# short_circuit_protection.net
KiCad netlist of a schematic drawn in Altium Designer
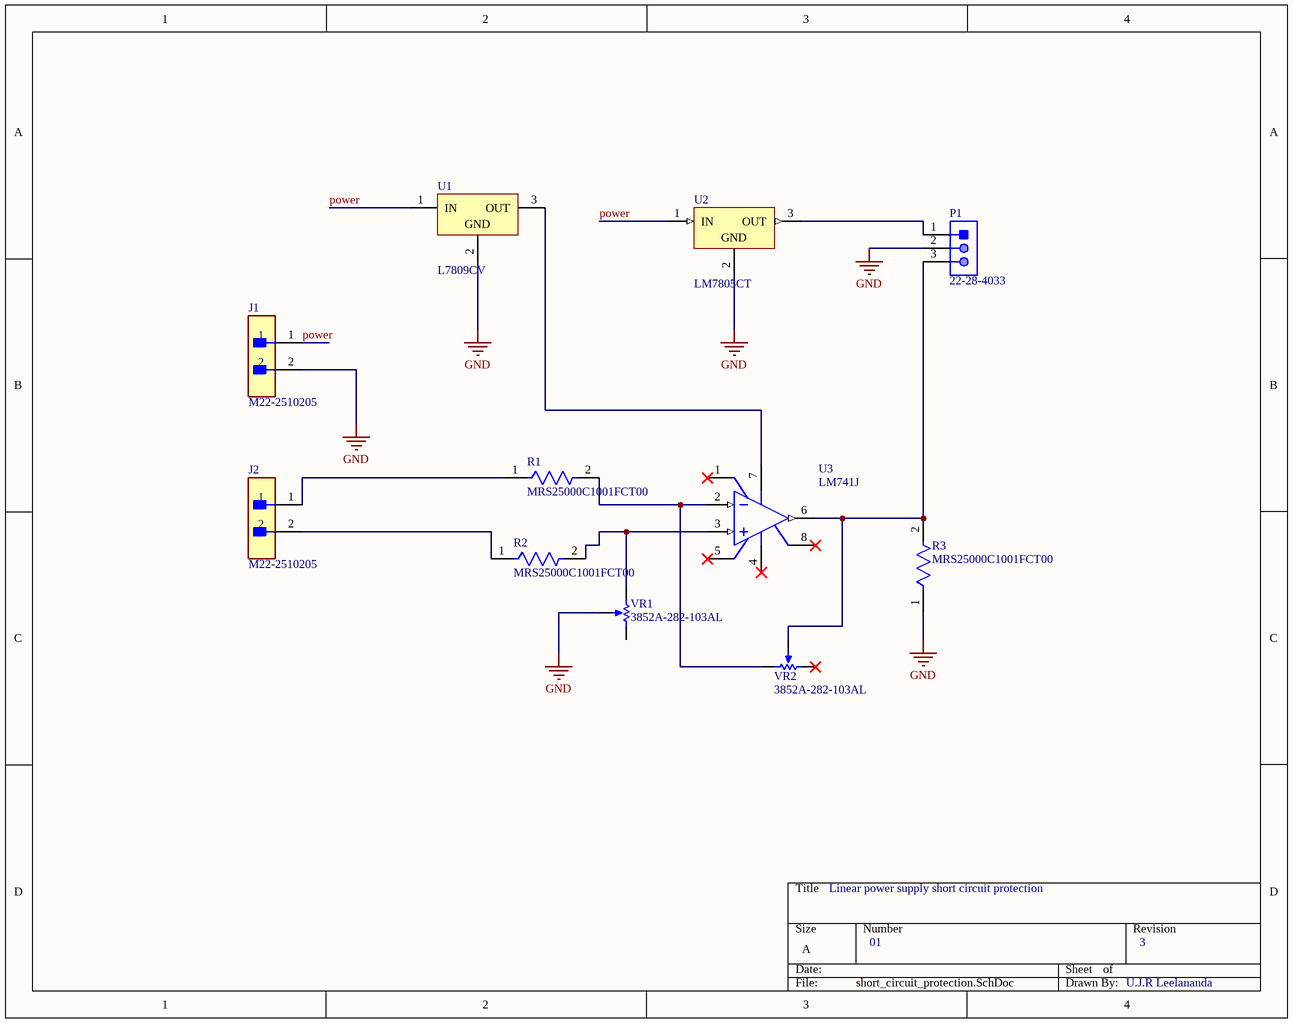
[diagram p0: short_circuit_protection.SchDoc]

(export (version "E")
  (design (tool "Eeschema 10.0.6"))
  (components
    (comp (ref "J1")
      (value "M22-2510205")
      (footprint "FP-M22-2510205-MFG")
      (description "CONN HEADER VERT 2POS 2MM")
      (fields
        (field (name "MANUFACTURER") "Harwin")
        (field (name "OCTOPART") "https://octopart.com/m22-2510205-harwin-2538221")
      )
      (libsource (lib "Altium Content Vault") (part "3bc925449376181038e59eaffc5286c"))
    )
    (comp (ref "J2")
      (value "M22-2510205")
      (footprint "FP-M22-2510205-MFG")
      (description "CONN HEADER VERT 2POS 2MM")
      (fields
        (field (name "MANUFACTURER") "Harwin")
        (field (name "OCTOPART") "https://octopart.com/m22-2510205-harwin-2538221")
      )
      (libsource (lib "Altium Content Vault") (part "3bc925449376181038e59eaffc5286c"))
    )
    (comp (ref "P1")
      (value "22-28-4033")
      (footprint "MOLX-22-28-4033_V")
      (description "Male Header, Pitch 2.54 mm, 1 x 3 Position, Height 8.38 mm, Tail Length 3.18 mm, RoHS, Bulk")
      (fields (field (name "MANUFACTURER") "Molex"))
      (libsource (lib "Altium Content Vault") (part "CN-1P-M-R3"))
    )
    (comp (ref "R1")
      (value "MRS25000C1001FCT00")
      (footprint "FP-MRS25-MFG")
      (description "RES 1K OHM 0.6W 1% AXIAL")
      (fields (field (name "TOLERANCE") "1%"))
      (libsource (lib "Altium Content Vault") (part "1029c3af85768c4190bb7ad29bc67b5"))
    )
    (comp (ref "R2")
      (value "MRS25000C1001FCT00")
      (footprint "FP-MRS25-MFG")
      (description "RES 1K OHM 0.6W 1% AXIAL")
      (fields (field (name "TOLERANCE") "1%"))
      (libsource (lib "Altium Content Vault") (part "1029c3af85768c4190bb7ad29bc67b5"))
    )
    (comp (ref "R3")
      (value "MRS25000C1001FCT00")
      (footprint "FP-MRS25-MFG")
      (description "RES 1K OHM 0.6W 1% AXIAL")
      (fields (field (name "TOLERANCE") "1%"))
      (libsource (lib "Altium Content Vault") (part "1029c3af85768c4190bb7ad29bc67b5"))
    )
    (comp (ref "U1")
      (value "L7809CV")
      (footprint "TO220")
      (description "Positive Voltage Regulator, 9V, 3-Pin TO-220")
      (libsource (lib "Altium Content Vault") (part "PM-REG-L4940-SIL3"))
    )
    (comp (ref "U2")
      (value "LM7805CT")
      (footprint "FAIR-TO-220-3")
      (description "Positive Voltage Regulator, 5 V, 1 A, -40 to 125 degC, 3-Pin TO-220, RoHS, Tube")
      (fields (field (name "MANUFACTURER") "FairchildSemiconductor"))
      (libsource (lib "Altium Content Vault") (part "FAIR-LM7805CT-TO220-3"))
    )
    (comp (ref "U3")
      (value "LM741J")
      (footprint "NAB0008A")
      (description "Operational Amplifier, 8-pin CerDIP")
      (fields (field (name "MANUFACTURER") "Texas Instruments"))
      (libsource (lib "Altium Content Vault") (part "AMP-OPA-LM741-8"))
    )
    (comp (ref "VR1")
      (value "3852A-282-103AL")
      (footprint "BOUR-3852A-282-103AL-3_V")
      (description "Diameter Panel Control, 10 KOhm, +/- 10%, 2 W, -1 to 125 degC, 3-Pin THD, RoHS, Bulk")
      (fields (field (name "TOLERANCE") "±10%") (field (name "MANUFACTURER") "Bourns"))
      (libsource (lib "Altium Content Vault") (part "RES-POT-3"))
    )
    (comp (ref "VR2")
      (value "3852A-282-103AL")
      (footprint "BOUR-3852A-282-103AL-3_V")
      (description "Diameter Panel Control, 10 KOhm, +/- 10%, 2 W, -1 to 125 degC, 3-Pin THD, RoHS, Bulk")
      (fields (field (name "TOLERANCE") "±10%") (field (name "MANUFACTURER") "Bourns"))
      (libsource (lib "Altium Content Vault") (part "RES-POT-3"))
    )
  )
  (nets
    (net (code "1") (name "/power") (class "Default")
      (node (ref "J1") (pin "1") (pinfunction "1_1") (pintype "passive"))
      (node (ref "U1") (pin "1") (pinfunction "IN_1") (pintype "power_in"))
      (node (ref "U2") (pin "1") (pinfunction "IN_1") (pintype "input"))
    )
    (net (code "2") (name "GND") (class "Default")
      (node (ref "J1") (pin "2") (pinfunction "2_2") (pintype "passive"))
      (node (ref "P1") (pin "2") (pinfunction "2_2") (pintype "passive"))
      (node (ref "R3") (pin "1") (pinfunction "1_1") (pintype "passive"))
      (node (ref "U1") (pin "2") (pinfunction "GND_2") (pintype "power_in"))
      (node (ref "U2") (pin "2") (pinfunction "GND_2") (pintype "power_in"))
      (node (ref "VR1") (pin "2") (pinfunction "S_2") (pintype "passive"))
    )
    (net (code "3") (name "Net-(J2-Pad1)") (class "Default")
      (node (ref "J2") (pin "1") (pinfunction "1_1") (pintype "passive"))
      (node (ref "R1") (pin "1") (pinfunction "1_1") (pintype "passive"))
    )
    (net (code "4") (name "Net-(J2-Pad2)") (class "Default")
      (node (ref "J2") (pin "2") (pinfunction "2_2") (pintype "passive"))
      (node (ref "R2") (pin "1") (pinfunction "1_1") (pintype "passive"))
    )
    (net (code "5") (name "Net-(U1-OUT)") (class "Default")
      (node (ref "U1") (pin "3") (pinfunction "OUT_3") (pintype "power_in"))
      (node (ref "U3") (pin "7") (pinfunction "V+_7") (pintype "power_in"))
    )
    (net (code "6") (name "Net-(U2-OUT)") (class "Default")
      (node (ref "P1") (pin "1") (pinfunction "1_1") (pintype "passive"))
      (node (ref "U2") (pin "3") (pinfunction "OUT_3") (pintype "output"))
    )
    (net (code "7") (name "Net-(U3-IN+)") (class "Default")
      (node (ref "R2") (pin "2") (pinfunction "2_2") (pintype "passive"))
      (node (ref "U3") (pin "3") (pinfunction "IN+_3") (pintype "input"))
      (node (ref "VR1") (pin "1") (pinfunction "CCW_1") (pintype "passive"))
    )
    (net (code "8") (name "Net-(U3-IN-)") (class "Default")
      (node (ref "R1") (pin "2") (pinfunction "2_2") (pintype "passive"))
      (node (ref "U3") (pin "2") (pinfunction "IN-_2") (pintype "input"))
      (node (ref "VR2") (pin "3") (pinfunction "CW_3") (pintype "passive"))
    )
    (net (code "9") (name "Net-(U3-OUT)") (class "Default")
      (node (ref "P1") (pin "3") (pinfunction "3_3") (pintype "passive"))
      (node (ref "R3") (pin "2") (pinfunction "2_2") (pintype "passive"))
      (node (ref "U3") (pin "6") (pinfunction "OUT_6") (pintype "output"))
      (node (ref "VR2") (pin "2") (pinfunction "S_2") (pintype "passive"))
    )
    (net (code "10") (name "unconnected-(U3-NC-Pad8)") (class "Default")
      (node (ref "U3") (pin "8") (pinfunction "NC_8") (pintype "passive+no_connect"))
    )
    (net (code "11") (name "unconnected-(U3-OFS_NULL-Pad1)") (class "Default")
      (node (ref "U3") (pin "1") (pinfunction "OFS_NULL_1") (pintype "passive+no_connect"))
    )
    (net (code "12") (name "unconnected-(U3-OFS_NULL-Pad5)") (class "Default")
      (node (ref "U3") (pin "5") (pinfunction "OFS_NULL_5") (pintype "passive+no_connect"))
    )
    (net (code "13") (name "unconnected-(U3-V--Pad4)") (class "Default")
      (node (ref "U3") (pin "4") (pinfunction "V-_4") (pintype "power_in+no_connect"))
    )
    (net (code "14") (name "unconnected-(VR1-CW-Pad3)") (class "Default")
      (node (ref "VR1") (pin "3") (pinfunction "CW_3") (pintype "passive"))
    )
    (net (code "15") (name "unconnected-(VR2-CCW-Pad1)") (class "Default")
      (node (ref "VR2") (pin "1") (pinfunction "CCW_1") (pintype "passive+no_connect"))
    )
  )
)
